# Clock_Extension.net
KiCad netlist of a schematic drawn in EAGLE
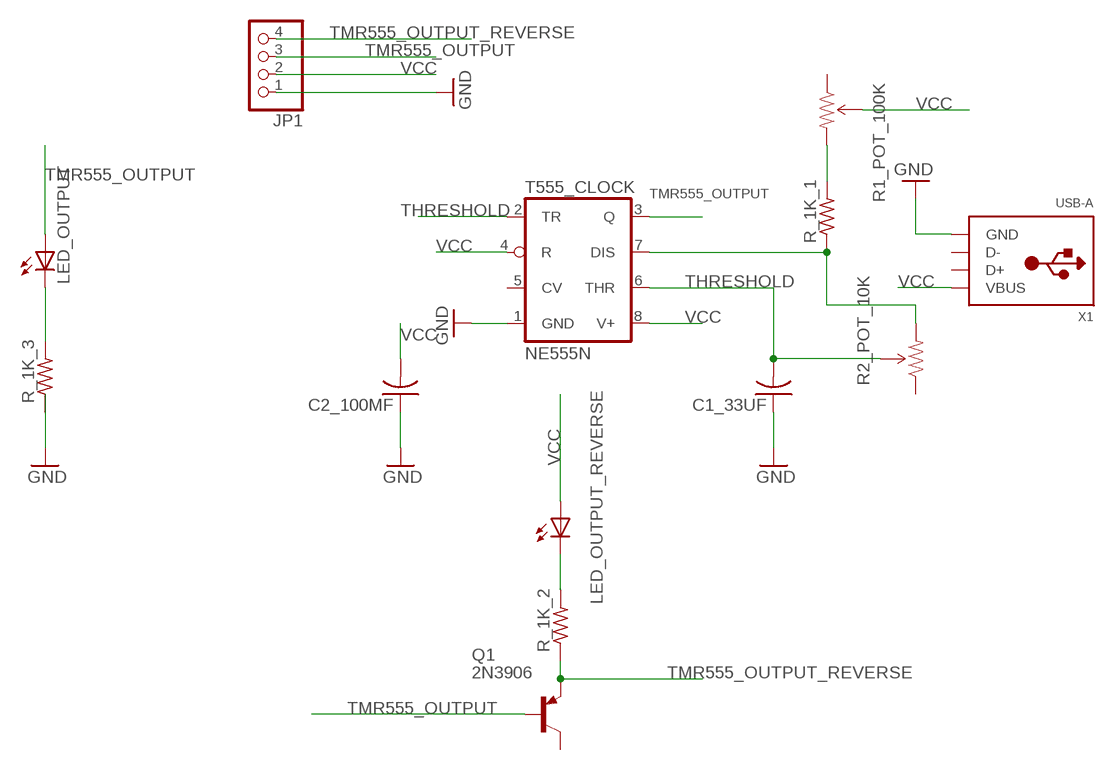
[diagram p0: schematic, sheet 1]

(export (version "E")
  (design (tool "Eeschema 10.0.6"))
  (components
    (comp (ref "C1_33UF")
      (value "C-US025-030X050")
      (footprint "eagle-import:C025-030X050")
      (libsource (lib "eagle-import") (part "C-US025-030X050"))
    )
    (comp (ref "C2_100MF")
      (value "C-US025-030X050")
      (footprint "eagle-import:C025-030X050")
      (libsource (lib "eagle-import") (part "C-US025-030X050"))
    )
    (comp (ref "JP1")
      (value "PINHD-1X4")
      (footprint "eagle-import:1X04")
      (libsource (lib "eagle-import") (part "PINHD-1X4"))
    )
    (comp (ref "LED_OUTPUT")
      (value "LEDSMT1206")
      (footprint "eagle-import:1206")
      (libsource (lib "eagle-import") (part "LEDSMT1206"))
    )
    (comp (ref "LED_OUTPUT_REVERSE")
      (value "LEDSMT1206")
      (footprint "eagle-import:1206")
      (libsource (lib "eagle-import") (part "LEDSMT1206"))
    )
    (comp (ref "Q1")
      (value "2N3906")
      (footprint "eagle-import:TO92")
      (libsource (lib "eagle-import") (part "2N3906"))
    )
    (comp (ref "R1_POT_100K")
      (value "TRIMPOTPTH")
      (footprint "eagle-import:TRIM_POT_PTH")
      (libsource (lib "eagle-import") (part "TRIMPOTPTH"))
    )
    (comp (ref "R2_POT_10K")
      (value "TRIMPOTPTH")
      (footprint "eagle-import:TRIM_POT_PTH")
      (libsource (lib "eagle-import") (part "TRIMPOTPTH"))
    )
    (comp (ref "R_1K_1")
      (value "R-US_R1206")
      (footprint "eagle-import:R1206")
      (libsource (lib "eagle-import") (part "R-US_R1206"))
    )
    (comp (ref "R_1K_2")
      (value "R-US_R1206")
      (footprint "eagle-import:R1206")
      (libsource (lib "eagle-import") (part "R-US_R1206"))
    )
    (comp (ref "R_1K_3")
      (value "R-US_R1206")
      (footprint "eagle-import:R1206")
      (libsource (lib "eagle-import") (part "R-US_R1206"))
    )
    (comp (ref "T555_CLOCK")
      (value "NE555N")
      (footprint "eagle-import:DIL08")
      (libsource (lib "eagle-import") (part "555NNE"))
    )
    (comp (ref "X1")
      (value "USB-A")
      (footprint "eagle-import:MOLEX_480371000")
      (libsource (lib "eagle-import") (part "USB-A"))
    )
  )
  (nets
    (net (code "1") (name "/THRESHOLD") (class "Default")
      (node (ref "C1_33UF") (pin "2") (pinfunction "2_2") (pintype "passive"))
      (node (ref "R2_POT_10K") (pin "2") (pinfunction "WIPER_2") (pintype "passive"))
      (node (ref "T555_CLOCK") (pin "2") (pinfunction "TR_2") (pintype "input"))
      (node (ref "T555_CLOCK") (pin "6") (pinfunction "THR_6") (pintype "input"))
    )
    (net (code "2") (name "/TMR555_OUTPUT") (class "Default")
      (node (ref "JP1") (pin "3") (pinfunction "3_3") (pintype "passive"))
      (node (ref "LED_OUTPUT") (pin "A") (pinfunction "A_A") (pintype "passive"))
      (node (ref "Q1") (pin "2") (pinfunction "B_2") (pintype "passive"))
      (node (ref "T555_CLOCK") (pin "3") (pinfunction "Q_3") (pintype "output"))
    )
    (net (code "3") (name "/TMR555_OUTPUT_REVERSE") (class "Default")
      (node (ref "JP1") (pin "4") (pinfunction "4_4") (pintype "passive"))
      (node (ref "Q1") (pin "3") (pinfunction "E_3") (pintype "passive"))
      (node (ref "R_1K_2") (pin "1") (pinfunction "1_1") (pintype "passive"))
    )
    (net (code "4") (name "/VCC") (class "Default")
      (node (ref "C2_100MF") (pin "2") (pinfunction "2_2") (pintype "passive"))
      (node (ref "JP1") (pin "2") (pinfunction "2_2") (pintype "passive"))
      (node (ref "LED_OUTPUT_REVERSE") (pin "A") (pinfunction "A_A") (pintype "passive"))
      (node (ref "R1_POT_100K") (pin "2") (pinfunction "WIPER_2") (pintype "passive"))
      (node (ref "T555_CLOCK") (pin "4") (pinfunction "R_4") (pintype "input"))
      (node (ref "T555_CLOCK") (pin "8") (pinfunction "V+_8") (pintype "power_in"))
      (node (ref "X1") (pin "1") (pinfunction "VBUS_1") (pintype "power_in"))
    )
    (net (code "5") (name "GND") (class "Default")
      (node (ref "C1_33UF") (pin "1") (pinfunction "1_1") (pintype "passive"))
      (node (ref "C2_100MF") (pin "1") (pinfunction "1_1") (pintype "passive"))
      (node (ref "JP1") (pin "1") (pinfunction "1_1") (pintype "passive"))
      (node (ref "R_1K_3") (pin "1") (pinfunction "1_1") (pintype "passive"))
      (node (ref "T555_CLOCK") (pin "1") (pinfunction "GND_1") (pintype "power_in"))
      (node (ref "X1") (pin "4") (pinfunction "GND_4") (pintype "power_in"))
    )
    (net (code "6") (name "Net-(LED_OUTPUT-PadC)") (class "Default")
      (node (ref "LED_OUTPUT") (pin "C") (pinfunction "C_C") (pintype "passive"))
      (node (ref "R_1K_3") (pin "2") (pinfunction "2_2") (pintype "passive"))
    )
    (net (code "7") (name "Net-(LED_OUTPUT_REVERSE-PadC)") (class "Default")
      (node (ref "LED_OUTPUT_REVERSE") (pin "C") (pinfunction "C_C") (pintype "passive"))
      (node (ref "R_1K_2") (pin "2") (pinfunction "2_2") (pintype "passive"))
    )
    (net (code "8") (name "Net-(R1_POT_100K-CW)") (class "Default")
      (node (ref "R1_POT_100K") (pin "3") (pinfunction "CW_3") (pintype "passive"))
      (node (ref "R_1K_1") (pin "2") (pinfunction "2_2") (pintype "passive"))
    )
    (net (code "9") (name "Net-(R2_POT_10K-CW)") (class "Default")
      (node (ref "R2_POT_10K") (pin "3") (pinfunction "CW_3") (pintype "passive"))
      (node (ref "R_1K_1") (pin "1") (pinfunction "1_1") (pintype "passive"))
      (node (ref "T555_CLOCK") (pin "7") (pinfunction "DIS_7") (pintype "input"))
    )
    (net (code "10") (name "unconnected-(Q1-C-Pad1)") (class "Default")
      (node (ref "Q1") (pin "1") (pinfunction "C_1") (pintype "passive"))
    )
    (net (code "11") (name "unconnected-(R1_POT_100K-CCW-Pad1)") (class "Default")
      (node (ref "R1_POT_100K") (pin "1") (pinfunction "CCW_1") (pintype "passive"))
    )
    (net (code "12") (name "unconnected-(R2_POT_10K-CCW-Pad1)") (class "Default")
      (node (ref "R2_POT_10K") (pin "1") (pinfunction "CCW_1") (pintype "passive"))
    )
    (net (code "13") (name "unconnected-(T555_CLOCK-CV-Pad5)") (class "Default")
      (node (ref "T555_CLOCK") (pin "5") (pinfunction "CV_5") (pintype "input"))
    )
    (net (code "14") (name "unconnected-(X1-D+-Pad3)") (class "Default")
      (node (ref "X1") (pin "3") (pinfunction "D+_3") (pintype "bidirectional"))
    )
    (net (code "15") (name "unconnected-(X1-D--Pad2)") (class "Default")
      (node (ref "X1") (pin "2") (pinfunction "D-_2") (pintype "bidirectional"))
    )
  )
)
